# Smart_Lights_X4.net
KiCad netlist of a schematic drawn in EAGLE
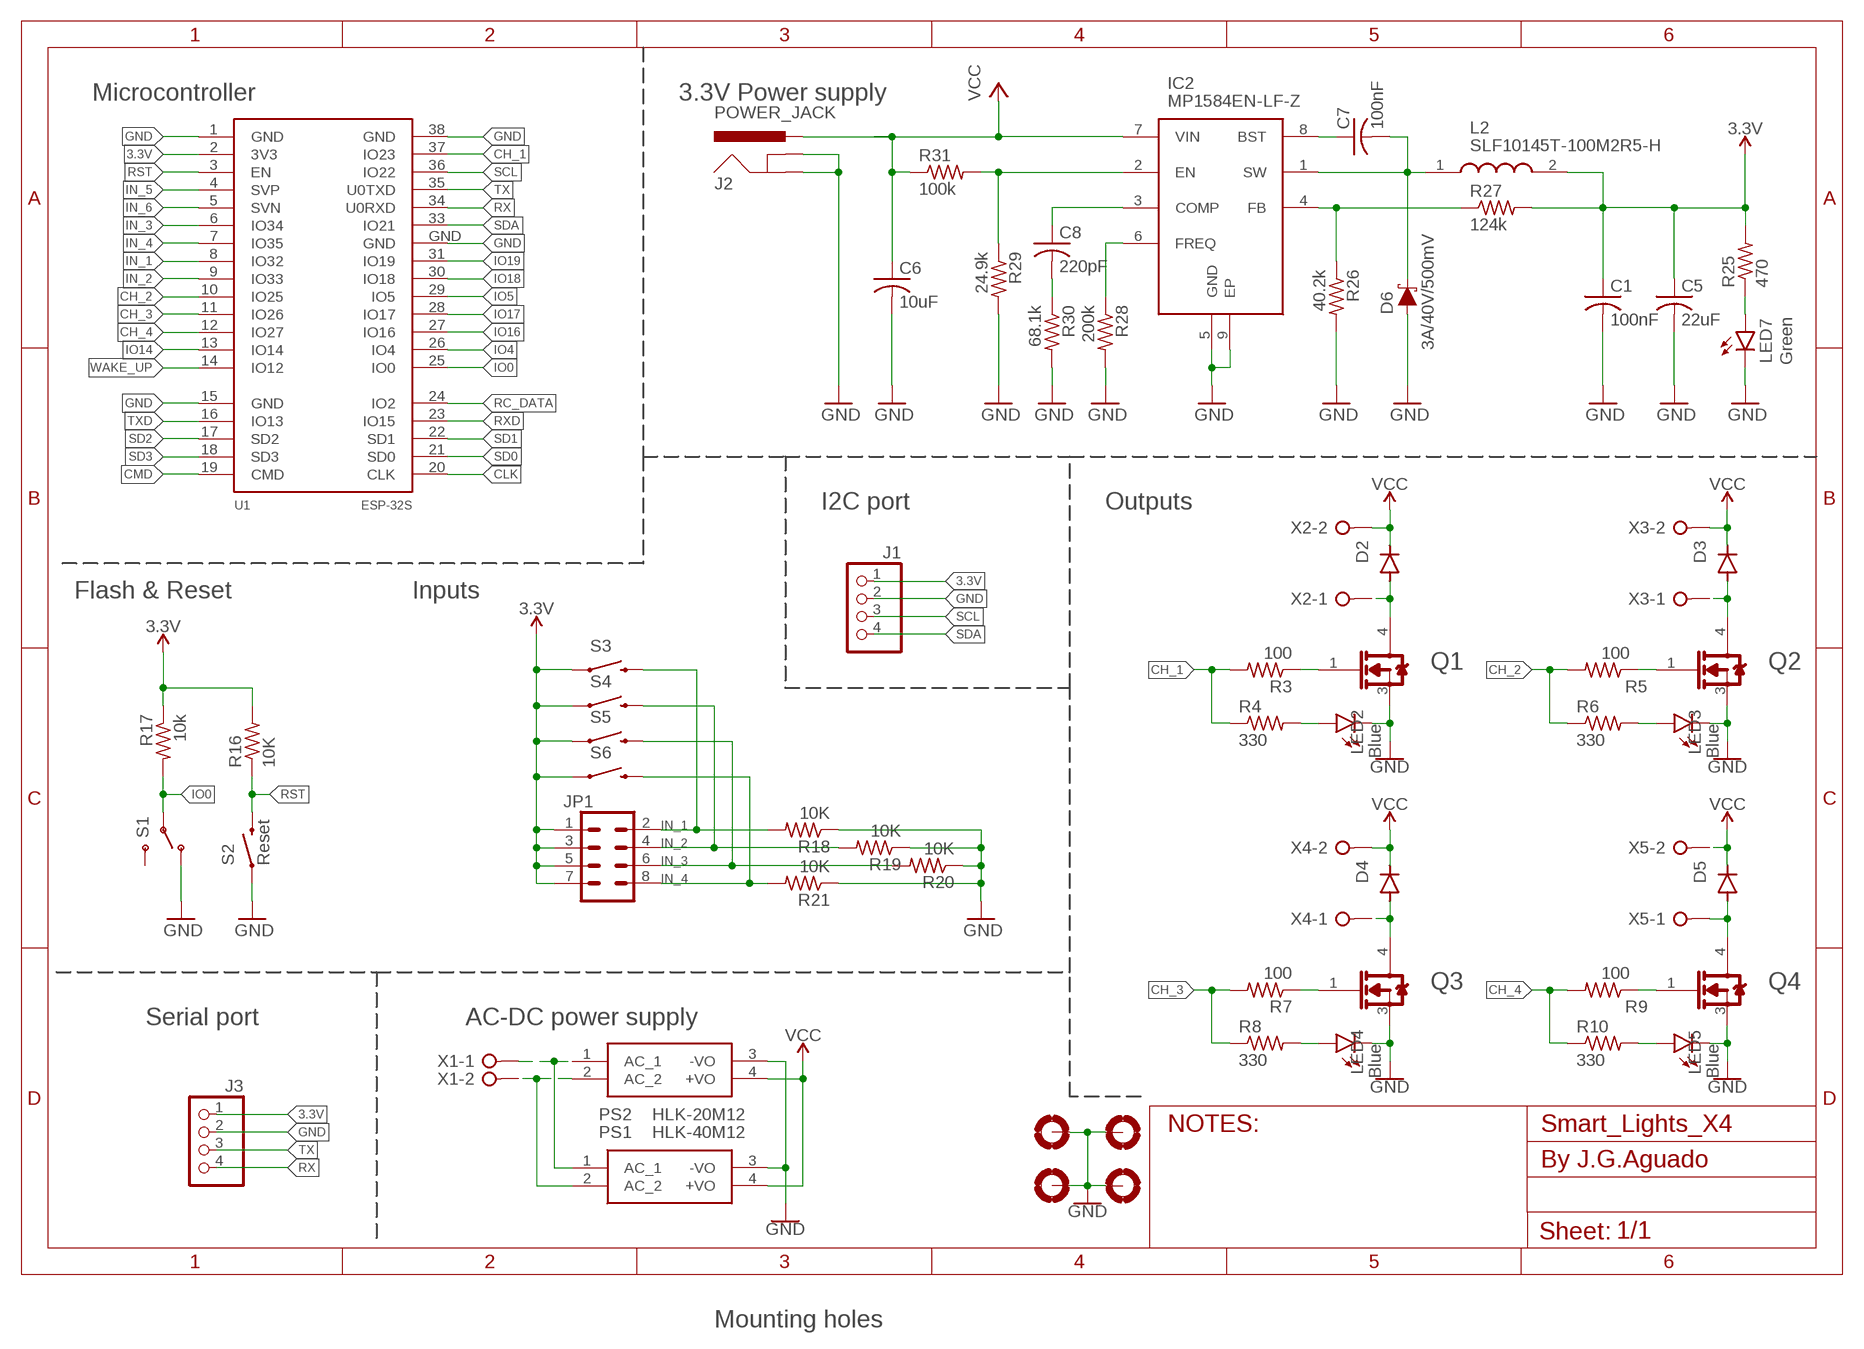
[diagram p0: schematic, sheet 1]

(export (version "E")
  (design (tool "Eeschema 10.0.6"))
  (components
    (comp (ref "C1")
      (value "100nF")
      (footprint "eagle-import:C0603")
      (libsource (lib "eagle-import") (part "C-USC0603"))
    )
    (comp (ref "C5")
      (value "22uF")
      (footprint "eagle-import:C0603")
      (libsource (lib "eagle-import") (part "C-USC0603"))
    )
    (comp (ref "C6")
      (value "10uF")
      (footprint "eagle-import:C0603")
      (libsource (lib "eagle-import") (part "C-USC0603"))
    )
    (comp (ref "C7")
      (value "100nF")
      (footprint "eagle-import:C0603")
      (libsource (lib "eagle-import") (part "C-USC0603"))
    )
    (comp (ref "C8")
      (value "220pF")
      (footprint "eagle-import:C0603")
      (libsource (lib "eagle-import") (part "C-USC0603"))
    )
    (comp (ref "D2")
      (value "DIODE-SOD123")
      (footprint "eagle-import:SOD123")
      (libsource (lib "eagle-import") (part "DIODE-SOD123"))
    )
    (comp (ref "D3")
      (value "DIODE-SOD123")
      (footprint "eagle-import:SOD123")
      (libsource (lib "eagle-import") (part "DIODE-SOD123"))
    )
    (comp (ref "D4")
      (value "DIODE-SOD123")
      (footprint "eagle-import:SOD123")
      (libsource (lib "eagle-import") (part "DIODE-SOD123"))
    )
    (comp (ref "D5")
      (value "DIODE-SOD123")
      (footprint "eagle-import:SOD123")
      (libsource (lib "eagle-import") (part "DIODE-SOD123"))
    )
    (comp (ref "D6")
      (value "3A/40V/500mV")
      (footprint "eagle-import:SMA-DIODE")
      (libsource (lib "eagle-import") (part "DIODE-SCHOTTKY-B340A"))
    )
    (comp (ref "FRAME1")
      (value "A4L-LOC")
      (footprint "eagle-import:92X87")
      (libsource (lib "eagle-import") (part "A4L-LOC"))
    )
    (comp (ref "IC2")
      (value "MP1584EN-LF-Z")
      (footprint "eagle-import:SOIC127P600X170-9N")
      (fields (field (name "MOUSER_PART_NUMBER") "946-MP1584ENLFZ"))
      (libsource (lib "eagle-import") (part "MP1584EN-LF-Z"))
    )
    (comp (ref "J1")
      (value "PINHD-1X4")
      (footprint "eagle-import:1X04")
      (libsource (lib "eagle-import") (part "PINHD-1X4"))
    )
    (comp (ref "J2")
      (value "POWER_JACK")
      (footprint "eagle-import:POWER_JACK_PTH")
      (libsource (lib "eagle-import") (part "POWER_JACK"))
    )
    (comp (ref "J3")
      (value "PINHD-1X4")
      (footprint "eagle-import:1X04")
      (libsource (lib "eagle-import") (part "PINHD-1X4"))
    )
    (comp (ref "JP1")
      (value "CONN_04X2")
      (footprint "eagle-import:2X4")
      (libsource (lib "eagle-import") (part "CONN_04X2"))
    )
    (comp (ref "L2")
      (value "SLF10145T-100M2R5-H")
      (footprint "eagle-import:SLF10145")
      (fields (field (name "MOUSER_PART_NUMBER") "810-SLF10145T100M2R5"))
      (libsource (lib "eagle-import") (part "SLF10145T-100M2R5-H"))
    )
    (comp (ref "LED2")
      (value "Blue")
      (footprint "eagle-import:SML0603")
      (libsource (lib "eagle-import") (part "LEDSML0603"))
    )
    (comp (ref "LED3")
      (value "Blue")
      (footprint "eagle-import:SML0603")
      (libsource (lib "eagle-import") (part "LEDSML0603"))
    )
    (comp (ref "LED4")
      (value "Blue")
      (footprint "eagle-import:SML0603")
      (libsource (lib "eagle-import") (part "LEDSML0603"))
    )
    (comp (ref "LED5")
      (value "Blue")
      (footprint "eagle-import:SML0603")
      (libsource (lib "eagle-import") (part "LEDSML0603"))
    )
    (comp (ref "LED7")
      (value "Green")
      (footprint "eagle-import:SML0603")
      (libsource (lib "eagle-import") (part "LEDSML0603"))
    )
    (comp (ref "PS1")
      (value "HLK-40M12")
      (footprint "eagle-import:HLK-40M12")
      (libsource (lib "eagle-import") (part "HLK-40M12"))
    )
    (comp (ref "PS2")
      (value "HLK-20M12")
      (footprint "eagle-import:HLK-20M12")
      (libsource (lib "eagle-import") (part "HLK-20M12"))
    )
    (comp (ref "Q1")
      (value "IRLR2905TRPBF")
      (footprint "eagle-import:INFINEON_TECHNOLOGIES_IRLR2905TRPBF_0")
      (fields
        (field (name "DIGIKEY_PART_NUMBER") "IRLR2905PBFCT-ND")
        (field (name "MF") "Infineon Technologies")
        (field (name "MOUSER_PART_NUMBER") "942-IRLR2905TRPBF")
      )
      (libsource (lib "eagle-import") (part "INFINEON_TECHNOLOGIES_IRLR2905TRPBFINFINEON_TECHNOLOGIES_IRLR2905TRPBF_0_0"))
    )
    (comp (ref "Q2")
      (value "IRLR2905TRPBF")
      (footprint "eagle-import:INFINEON_TECHNOLOGIES_IRLR2905TRPBF_0")
      (fields
        (field (name "DIGIKEY_PART_NUMBER") "IRLR2905PBFCT-ND")
        (field (name "MF") "Infineon Technologies")
        (field (name "MOUSER_PART_NUMBER") "942-IRLR2905TRPBF")
      )
      (libsource (lib "eagle-import") (part "INFINEON_TECHNOLOGIES_IRLR2905TRPBFINFINEON_TECHNOLOGIES_IRLR2905TRPBF_0_0"))
    )
    (comp (ref "Q3")
      (value "IRLR2905TRPBF")
      (footprint "eagle-import:INFINEON_TECHNOLOGIES_IRLR2905TRPBF_0")
      (fields
        (field (name "DIGIKEY_PART_NUMBER") "IRLR2905PBFCT-ND")
        (field (name "MF") "Infineon Technologies")
        (field (name "MOUSER_PART_NUMBER") "942-IRLR2905TRPBF")
      )
      (libsource (lib "eagle-import") (part "INFINEON_TECHNOLOGIES_IRLR2905TRPBFINFINEON_TECHNOLOGIES_IRLR2905TRPBF_0_0"))
    )
    (comp (ref "Q4")
      (value "IRLR2905TRPBF")
      (footprint "eagle-import:INFINEON_TECHNOLOGIES_IRLR2905TRPBF_0")
      (fields
        (field (name "DIGIKEY_PART_NUMBER") "IRLR2905PBFCT-ND")
        (field (name "MF") "Infineon Technologies")
        (field (name "MOUSER_PART_NUMBER") "942-IRLR2905TRPBF")
      )
      (libsource (lib "eagle-import") (part "INFINEON_TECHNOLOGIES_IRLR2905TRPBFINFINEON_TECHNOLOGIES_IRLR2905TRPBF_0_0"))
    )
    (comp (ref "R3")
      (value "100")
      (footprint "eagle-import:R0603")
      (libsource (lib "eagle-import") (part "R-US_R0603"))
    )
    (comp (ref "R4")
      (value "330")
      (footprint "eagle-import:R0603")
      (libsource (lib "eagle-import") (part "R-US_R0603"))
    )
    (comp (ref "R5")
      (value "100")
      (footprint "eagle-import:R0603")
      (libsource (lib "eagle-import") (part "R-US_R0603"))
    )
    (comp (ref "R6")
      (value "330")
      (footprint "eagle-import:R0603")
      (libsource (lib "eagle-import") (part "R-US_R0603"))
    )
    (comp (ref "R7")
      (value "100")
      (footprint "eagle-import:R0603")
      (libsource (lib "eagle-import") (part "R-US_R0603"))
    )
    (comp (ref "R8")
      (value "330")
      (footprint "eagle-import:R0603")
      (libsource (lib "eagle-import") (part "R-US_R0603"))
    )
    (comp (ref "R9")
      (value "100")
      (footprint "eagle-import:R0603")
      (libsource (lib "eagle-import") (part "R-US_R0603"))
    )
    (comp (ref "R10")
      (value "330")
      (footprint "eagle-import:R0603")
      (libsource (lib "eagle-import") (part "R-US_R0603"))
    )
    (comp (ref "R16")
      (value "10K")
      (footprint "eagle-import:R0603")
      (libsource (lib "eagle-import") (part "R-US_R0603"))
    )
    (comp (ref "R17")
      (value "10k")
      (footprint "eagle-import:R0603")
      (libsource (lib "eagle-import") (part "R-US_R0603"))
    )
    (comp (ref "R18")
      (value "10K")
      (footprint "eagle-import:R0603")
      (libsource (lib "eagle-import") (part "R-US_R0603"))
    )
    (comp (ref "R19")
      (value "10K")
      (footprint "eagle-import:R0603")
      (libsource (lib "eagle-import") (part "R-US_R0603"))
    )
    (comp (ref "R20")
      (value "10K")
      (footprint "eagle-import:R0603")
      (libsource (lib "eagle-import") (part "R-US_R0603"))
    )
    (comp (ref "R21")
      (value "10K")
      (footprint "eagle-import:R0603")
      (libsource (lib "eagle-import") (part "R-US_R0603"))
    )
    (comp (ref "R25")
      (value "470")
      (footprint "eagle-import:R0603")
      (libsource (lib "eagle-import") (part "R-US_R0603"))
    )
    (comp (ref "R26")
      (value "40.2k")
      (footprint "eagle-import:R0603")
      (libsource (lib "eagle-import") (part "R-US_R0603"))
    )
    (comp (ref "R27")
      (value "124k")
      (footprint "eagle-import:R0603")
      (libsource (lib "eagle-import") (part "R-US_R0603"))
    )
    (comp (ref "R28")
      (value "200k")
      (footprint "eagle-import:R0603")
      (libsource (lib "eagle-import") (part "R-US_R0603"))
    )
    (comp (ref "R29")
      (value "24.9k")
      (footprint "eagle-import:R0603")
      (libsource (lib "eagle-import") (part "R-US_R0603"))
    )
    (comp (ref "R30")
      (value "68.1k")
      (footprint "eagle-import:R0603")
      (libsource (lib "eagle-import") (part "R-US_R0603"))
    )
    (comp (ref "R31")
      (value "100k")
      (footprint "eagle-import:R0603")
      (libsource (lib "eagle-import") (part "R-US_R0603"))
    )
    (comp (ref "S1")
      (value "SWITCH_SPDT")
      (footprint "eagle-import:KPS-1290")
      (libsource (lib "eagle-import") (part "SWITCH_SPDT"))
    )
    (comp (ref "S2")
      (value "Reset")
      (footprint "eagle-import:TACTILE_SWITCH_TALL")
      (libsource (lib "eagle-import") (part "SWITCH-MOMENTARY-2SMD-4"))
    )
    (comp (ref "S3")
      (value "Reset")
      (footprint "eagle-import:TACTILE_SWITCH_TALL")
      (libsource (lib "eagle-import") (part "SWITCH-MOMENTARY-2SMD-4"))
    )
    (comp (ref "S4")
      (value "Reset")
      (footprint "eagle-import:TACTILE_SWITCH_TALL")
      (libsource (lib "eagle-import") (part "SWITCH-MOMENTARY-2SMD-4"))
    )
    (comp (ref "S5")
      (value "Reset")
      (footprint "eagle-import:TACTILE_SWITCH_TALL")
      (libsource (lib "eagle-import") (part "SWITCH-MOMENTARY-2SMD-4"))
    )
    (comp (ref "S6")
      (value "Reset")
      (footprint "eagle-import:TACTILE_SWITCH_TALL")
      (libsource (lib "eagle-import") (part "SWITCH-MOMENTARY-2SMD-4"))
    )
    (comp (ref "U1")
      (value "ESP-32S")
      (footprint "eagle-import:ESP-32S")
      (libsource (lib "eagle-import") (part "ESP-32S"))
    )
    (comp (ref "X1")
      (value "W237-02P")
      (footprint "eagle-import:W237-132")
      (libsource (lib "eagle-import") (part "W237-02P"))
    )
    (comp (ref "X2")
      (value "W237-02P")
      (footprint "eagle-import:W237-132")
      (libsource (lib "eagle-import") (part "W237-02P"))
    )
    (comp (ref "X3")
      (value "W237-02P")
      (footprint "eagle-import:W237-132")
      (libsource (lib "eagle-import") (part "W237-02P"))
    )
    (comp (ref "X4")
      (value "W237-02P")
      (footprint "eagle-import:W237-132")
      (libsource (lib "eagle-import") (part "W237-02P"))
    )
    (comp (ref "X5")
      (value "W237-02P")
      (footprint "eagle-import:W237-132")
      (libsource (lib "eagle-import") (part "W237-02P"))
    )
  )
  (nets
    (net (code "1") (name "3.3V") (class "Default")
      (node (ref "C1") (pin "1") (pinfunction "1_1") (pintype "passive"))
      (node (ref "C5") (pin "1") (pinfunction "1_1") (pintype "passive"))
      (node (ref "J1") (pin "1") (pinfunction "1_1") (pintype "passive"))
      (node (ref "J3") (pin "1") (pinfunction "1_1") (pintype "passive"))
      (node (ref "JP1") (pin "1") (pinfunction "1_1") (pintype "passive"))
      (node (ref "JP1") (pin "3") (pinfunction "3_3") (pintype "passive"))
      (node (ref "JP1") (pin "5") (pinfunction "5_5") (pintype "passive"))
      (node (ref "JP1") (pin "7") (pinfunction "7_7") (pintype "passive"))
      (node (ref "L2") (pin "2") (pinfunction "2_2") (pintype "bidirectional"))
      (node (ref "R16") (pin "2") (pinfunction "2_2") (pintype "passive"))
      (node (ref "R17") (pin "1") (pinfunction "1_1") (pintype "passive"))
      (node (ref "R25") (pin "2") (pinfunction "2_2") (pintype "passive"))
      (node (ref "R27") (pin "2") (pinfunction "2_2") (pintype "passive"))
      (node (ref "S3") (pin "A2") (pinfunction "1_A2") (pintype "passive"))
      (node (ref "S4") (pin "A2") (pinfunction "1_A2") (pintype "passive"))
      (node (ref "S5") (pin "A2") (pinfunction "1_A2") (pintype "passive"))
      (node (ref "S6") (pin "A2") (pinfunction "1_A2") (pintype "passive"))
      (node (ref "U1") (pin "2") (pinfunction "3V3_2") (pintype "power_in"))
    )
    (net (code "2") (name "CH_1") (class "Default")
      (node (ref "R3") (pin "2") (pinfunction "2_2") (pintype "passive"))
      (node (ref "R4") (pin "1") (pinfunction "1_1") (pintype "passive"))
      (node (ref "U1") (pin "37") (pinfunction "IO23_37") (pintype "bidirectional"))
    )
    (net (code "3") (name "CH_2") (class "Default")
      (node (ref "R5") (pin "2") (pinfunction "2_2") (pintype "passive"))
      (node (ref "R6") (pin "1") (pinfunction "1_1") (pintype "passive"))
      (node (ref "U1") (pin "10") (pinfunction "IO25_10") (pintype "bidirectional"))
    )
    (net (code "4") (name "CH_3") (class "Default")
      (node (ref "R7") (pin "2") (pinfunction "2_2") (pintype "passive"))
      (node (ref "R8") (pin "1") (pinfunction "1_1") (pintype "passive"))
      (node (ref "U1") (pin "11") (pinfunction "IO26_11") (pintype "bidirectional"))
    )
    (net (code "5") (name "CH_4") (class "Default")
      (node (ref "R10") (pin "1") (pinfunction "1_1") (pintype "passive"))
      (node (ref "R9") (pin "2") (pinfunction "2_2") (pintype "passive"))
      (node (ref "U1") (pin "12") (pinfunction "IO27_12") (pintype "bidirectional"))
    )
    (net (code "6") (name "CLK") (class "Default")
      (node (ref "U1") (pin "20") (pinfunction "CLK_20") (pintype "bidirectional"))
    )
    (net (code "7") (name "CMD") (class "Default")
      (node (ref "U1") (pin "19") (pinfunction "CMD_19") (pintype "bidirectional"))
    )
    (net (code "8") (name "GND") (class "Default")
      (node (ref "C1") (pin "2") (pinfunction "2_2") (pintype "passive"))
      (node (ref "C5") (pin "2") (pinfunction "2_2") (pintype "passive"))
      (node (ref "C6") (pin "2") (pinfunction "2_2") (pintype "passive"))
      (node (ref "D6") (pin "A") (pinfunction "A_A") (pintype "passive"))
      (node (ref "FRAME1") (pin "B3,1") (pinfunction "MOUNT_B3,1") (pintype "passive"))
      (node (ref "FRAME1") (pin "B3,2") (pinfunction "MOUNT1_B3,2") (pintype "passive"))
      (node (ref "FRAME1") (pin "B3,3") (pinfunction "MOUNT2_B3,3") (pintype "passive"))
      (node (ref "FRAME1") (pin "B3,6") (pinfunction "MOUNT3_B3,6") (pintype "passive"))
      (node (ref "IC2") (pin "5") (pinfunction "GND_5") (pintype "power_in"))
      (node (ref "IC2") (pin "9") (pinfunction "EP_9") (pintype "bidirectional"))
      (node (ref "J1") (pin "2") (pinfunction "2_2") (pintype "passive"))
      (node (ref "J2") (pin "GND") (pinfunction "GND_GND") (pintype "bidirectional"))
      (node (ref "J2") (pin "GNDBREAK") (pinfunction "GNDBREAK_GNDBREAK") (pintype "bidirectional"))
      (node (ref "J3") (pin "2") (pinfunction "2_2") (pintype "passive"))
      (node (ref "LED2") (pin "C") (pinfunction "C_C") (pintype "passive"))
      (node (ref "LED3") (pin "C") (pinfunction "C_C") (pintype "passive"))
      (node (ref "LED4") (pin "C") (pinfunction "C_C") (pintype "passive"))
      (node (ref "LED5") (pin "C") (pinfunction "C_C") (pintype "passive"))
      (node (ref "LED7") (pin "C") (pinfunction "C_C") (pintype "passive"))
      (node (ref "PS1") (pin "3") (pinfunction "-VO_3") (pintype "bidirectional"))
      (node (ref "PS2") (pin "3") (pinfunction "-VO_3") (pintype "bidirectional"))
      (node (ref "Q1") (pin "3") (pinfunction "SOURCE_3") (pintype "passive"))
      (node (ref "Q2") (pin "3") (pinfunction "SOURCE_3") (pintype "passive"))
      (node (ref "Q3") (pin "3") (pinfunction "SOURCE_3") (pintype "passive"))
      (node (ref "Q4") (pin "3") (pinfunction "SOURCE_3") (pintype "passive"))
      (node (ref "R18") (pin "1") (pinfunction "1_1") (pintype "passive"))
      (node (ref "R19") (pin "1") (pinfunction "1_1") (pintype "passive"))
      (node (ref "R20") (pin "1") (pinfunction "1_1") (pintype "passive"))
      (node (ref "R21") (pin "1") (pinfunction "1_1") (pintype "passive"))
      (node (ref "R26") (pin "2") (pinfunction "2_2") (pintype "passive"))
      (node (ref "R28") (pin "2") (pinfunction "2_2") (pintype "passive"))
      (node (ref "R29") (pin "2") (pinfunction "2_2") (pintype "passive"))
      (node (ref "R30") (pin "2") (pinfunction "2_2") (pintype "passive"))
      (node (ref "S1") (pin "O") (pinfunction "O_O") (pintype "passive"))
      (node (ref "S2") (pin "A2") (pinfunction "1_A2") (pintype "passive"))
      (node (ref "U1") (pin "1") (pinfunction "GND_1") (pintype "power_in"))
      (node (ref "U1") (pin "15") (pinfunction "GND_15") (pintype "power_in"))
      (node (ref "U1") (pin "38") (pinfunction "GND_38") (pintype "power_in"))
      (node (ref "U1") (pin "GND") (pinfunction "GND_GND") (pintype "power_in"))
    )
    (net (code "9") (name "IN_1") (class "Default")
      (node (ref "JP1") (pin "2") (pinfunction "2_2") (pintype "passive"))
      (node (ref "R18") (pin "2") (pinfunction "2_2") (pintype "passive"))
      (node (ref "S3") (pin "B2") (pinfunction "2_B2") (pintype "passive"))
      (node (ref "U1") (pin "8") (pinfunction "IO32_8") (pintype "bidirectional"))
    )
    (net (code "10") (name "IN_2") (class "Default")
      (node (ref "JP1") (pin "4") (pinfunction "4_4") (pintype "passive"))
      (node (ref "R19") (pin "2") (pinfunction "2_2") (pintype "passive"))
      (node (ref "S4") (pin "B2") (pinfunction "2_B2") (pintype "passive"))
      (node (ref "U1") (pin "9") (pinfunction "IO33_9") (pintype "bidirectional"))
    )
    (net (code "11") (name "IN_3") (class "Default")
      (node (ref "JP1") (pin "6") (pinfunction "6_6") (pintype "passive"))
      (node (ref "R20") (pin "2") (pinfunction "2_2") (pintype "passive"))
      (node (ref "S5") (pin "B2") (pinfunction "2_B2") (pintype "passive"))
      (node (ref "U1") (pin "6") (pinfunction "IO34_6") (pintype "bidirectional"))
    )
    (net (code "12") (name "IN_4") (class "Default")
      (node (ref "JP1") (pin "8") (pinfunction "8_8") (pintype "passive"))
      (node (ref "R21") (pin "2") (pinfunction "2_2") (pintype "passive"))
      (node (ref "S6") (pin "B2") (pinfunction "2_B2") (pintype "passive"))
      (node (ref "U1") (pin "7") (pinfunction "IO35_7") (pintype "bidirectional"))
    )
    (net (code "13") (name "IN_5") (class "Default")
      (node (ref "U1") (pin "4") (pinfunction "SVP_4") (pintype "bidirectional"))
    )
    (net (code "14") (name "IN_6") (class "Default")
      (node (ref "U1") (pin "5") (pinfunction "SVN_5") (pintype "bidirectional"))
    )
    (net (code "15") (name "IO0") (class "Default")
      (node (ref "R17") (pin "2") (pinfunction "2_2") (pintype "passive"))
      (node (ref "S1") (pin "P") (pinfunction "P_P") (pintype "passive"))
      (node (ref "U1") (pin "25") (pinfunction "IO0_25") (pintype "bidirectional"))
    )
    (net (code "16") (name "IO4") (class "Default")
      (node (ref "U1") (pin "26") (pinfunction "IO4_26") (pintype "bidirectional"))
    )
    (net (code "17") (name "IO5") (class "Default")
      (node (ref "U1") (pin "29") (pinfunction "IO5_29") (pintype "bidirectional"))
    )
    (net (code "18") (name "IO14") (class "Default")
      (node (ref "U1") (pin "13") (pinfunction "IO14_13") (pintype "bidirectional"))
    )
    (net (code "19") (name "IO16") (class "Default")
      (node (ref "U1") (pin "27") (pinfunction "IO16_27") (pintype "bidirectional"))
    )
    (net (code "20") (name "IO17") (class "Default")
      (node (ref "U1") (pin "28") (pinfunction "IO17_28") (pintype "bidirectional"))
    )
    (net (code "21") (name "IO18") (class "Default")
      (node (ref "U1") (pin "30") (pinfunction "IO18_30") (pintype "bidirectional"))
    )
    (net (code "22") (name "IO19") (class "Default")
      (node (ref "U1") (pin "31") (pinfunction "IO19_31") (pintype "bidirectional"))
    )
    (net (code "23") (name "Net-(C8-Pad2)") (class "Default")
      (node (ref "C8") (pin "2") (pinfunction "2_2") (pintype "passive"))
      (node (ref "R30") (pin "1") (pinfunction "1_1") (pintype "passive"))
    )
    (net (code "24") (name "Net-(IC2-BST)") (class "Default")
      (node (ref "C7") (pin "1") (pinfunction "1_1") (pintype "passive"))
      (node (ref "IC2") (pin "8") (pinfunction "BST_8") (pintype "input"))
    )
    (net (code "25") (name "Net-(IC2-COMP)") (class "Default")
      (node (ref "C8") (pin "1") (pinfunction "1_1") (pintype "passive"))
      (node (ref "IC2") (pin "3") (pinfunction "COMP_3") (pintype "bidirectional"))
    )
    (net (code "26") (name "Net-(IC2-EN)") (class "Default")
      (node (ref "IC2") (pin "2") (pinfunction "EN_2") (pintype "input"))
      (node (ref "R29") (pin "1") (pinfunction "1_1") (pintype "passive"))
      (node (ref "R31") (pin "2") (pinfunction "2_2") (pintype "passive"))
    )
    (net (code "27") (name "Net-(IC2-FB)") (class "Default")
      (node (ref "IC2") (pin "4") (pinfunction "FB_4") (pintype "input"))
      (node (ref "R26") (pin "1") (pinfunction "1_1") (pintype "passive"))
      (node (ref "R27") (pin "1") (pinfunction "1_1") (pintype "passive"))
    )
    (net (code "28") (name "Net-(IC2-FREQ)") (class "Default")
      (node (ref "IC2") (pin "6") (pinfunction "FREQ_6") (pintype "input"))
      (node (ref "R28") (pin "1") (pinfunction "1_1") (pintype "passive"))
    )
    (net (code "29") (name "Net-(IC2-SW)") (class "Default")
      (node (ref "C7") (pin "2") (pinfunction "2_2") (pintype "passive"))
      (node (ref "D6") (pin "C") (pinfunction "C_C") (pintype "passive"))
      (node (ref "IC2") (pin "1") (pinfunction "SW_1") (pintype "output"))
      (node (ref "L2") (pin "1") (pinfunction "1_1") (pintype "bidirectional"))
    )
    (net (code "30") (name "Net-(LED2-PadA)") (class "Default")
      (node (ref "LED2") (pin "A") (pinfunction "A_A") (pintype "passive"))
      (node (ref "R4") (pin "2") (pinfunction "2_2") (pintype "passive"))
    )
    (net (code "31") (name "Net-(LED3-PadA)") (class "Default")
      (node (ref "LED3") (pin "A") (pinfunction "A_A") (pintype "passive"))
      (node (ref "R6") (pin "2") (pinfunction "2_2") (pintype "passive"))
    )
    (net (code "32") (name "Net-(LED4-PadA)") (class "Default")
      (node (ref "LED4") (pin "A") (pinfunction "A_A") (pintype "passive"))
      (node (ref "R8") (pin "2") (pinfunction "2_2") (pintype "passive"))
    )
    (net (code "33") (name "Net-(LED5-PadA)") (class "Default")
      (node (ref "LED5") (pin "A") (pinfunction "A_A") (pintype "passive"))
      (node (ref "R10") (pin "2") (pinfunction "2_2") (pintype "passive"))
    )
    (net (code "34") (name "Net-(LED7-PadA)") (class "Default")
      (node (ref "LED7") (pin "A") (pinfunction "A_A") (pintype "passive"))
      (node (ref "R25") (pin "1") (pinfunction "1_1") (pintype "passive"))
    )
    (net (code "35") (name "Net-(PS1-AC_1)") (class "Default")
      (node (ref "PS1") (pin "1") (pinfunction "AC_1_1") (pintype "bidirectional"))
      (node (ref "PS2") (pin "1") (pinfunction "AC_1_1") (pintype "bidirectional"))
      (node (ref "X1") (pin "1") (pinfunction "KL_1") (pintype "passive"))
    )
    (net (code "36") (name "Net-(PS1-AC_2)") (class "Default")
      (node (ref "PS1") (pin "2") (pinfunction "AC_2_2") (pintype "bidirectional"))
      (node (ref "PS2") (pin "2") (pinfunction "AC_2_2") (pintype "bidirectional"))
      (node (ref "X1") (pin "2") (pinfunction "KL_2") (pintype "passive"))
    )
    (net (code "37") (name "Net-(Q1-DRAIN)") (class "Default")
      (node (ref "D2") (pin "A") (pinfunction "A_A") (pintype "passive"))
      (node (ref "Q1") (pin "4") (pinfunction "DRAIN_4") (pintype "passive"))
      (node (ref "X2") (pin "1") (pinfunction "KL_1") (pintype "passive"))
    )
    (net (code "38") (name "Net-(Q1-GATE)") (class "Default")
      (node (ref "Q1") (pin "1") (pinfunction "GATE_1") (pintype "passive"))
      (node (ref "R3") (pin "1") (pinfunction "1_1") (pintype "passive"))
    )
    (net (code "39") (name "Net-(Q2-DRAIN)") (class "Default")
      (node (ref "D3") (pin "A") (pinfunction "A_A") (pintype "passive"))
      (node (ref "Q2") (pin "4") (pinfunction "DRAIN_4") (pintype "passive"))
      (node (ref "X3") (pin "1") (pinfunction "KL_1") (pintype "passive"))
    )
    (net (code "40") (name "Net-(Q2-GATE)") (class "Default")
      (node (ref "Q2") (pin "1") (pinfunction "GATE_1") (pintype "passive"))
      (node (ref "R5") (pin "1") (pinfunction "1_1") (pintype "passive"))
    )
    (net (code "41") (name "Net-(Q3-DRAIN)") (class "Default")
      (node (ref "D4") (pin "A") (pinfunction "A_A") (pintype "passive"))
      (node (ref "Q3") (pin "4") (pinfunction "DRAIN_4") (pintype "passive"))
      (node (ref "X4") (pin "1") (pinfunction "KL_1") (pintype "passive"))
    )
    (net (code "42") (name "Net-(Q3-GATE)") (class "Default")
      (node (ref "Q3") (pin "1") (pinfunction "GATE_1") (pintype "passive"))
      (node (ref "R7") (pin "1") (pinfunction "1_1") (pintype "passive"))
    )
    (net (code "43") (name "Net-(Q4-DRAIN)") (class "Default")
      (node (ref "D5") (pin "A") (pinfunction "A_A") (pintype "passive"))
      (node (ref "Q4") (pin "4") (pinfunction "DRAIN_4") (pintype "passive"))
      (node (ref "X5") (pin "1") (pinfunction "KL_1") (pintype "passive"))
    )
    (net (code "44") (name "Net-(Q4-GATE)") (class "Default")
      (node (ref "Q4") (pin "1") (pinfunction "GATE_1") (pintype "passive"))
      (node (ref "R9") (pin "1") (pinfunction "1_1") (pintype "passive"))
    )
    (net (code "45") (name "RC_DATA") (class "Default")
      (node (ref "U1") (pin "24") (pinfunction "IO2_24") (pintype "bidirectional"))
    )
    (net (code "46") (name "RST") (class "Default")
      (node (ref "R16") (pin "1") (pinfunction "1_1") (pintype "passive"))
      (node (ref "S2") (pin "B2") (pinfunction "2_B2") (pintype "passive"))
      (node (ref "U1") (pin "3") (pinfunction "EN_3") (pintype "input"))
    )
    (net (code "47") (name "RX") (class "Default")
      (node (ref "J3") (pin "4") (pinfunction "4_4") (pintype "passive"))
      (node (ref "U1") (pin "34") (pinfunction "U0RXD_34") (pintype "bidirectional"))
    )
    (net (code "48") (name "RXD") (class "Default")
      (node (ref "U1") (pin "23") (pinfunction "IO15_23") (pintype "bidirectional"))
    )
    (net (code "49") (name "SCL") (class "Default")
      (node (ref "J1") (pin "3") (pinfunction "3_3") (pintype "passive"))
      (node (ref "U1") (pin "36") (pinfunction "IO22_36") (pintype "bidirectional"))
    )
    (net (code "50") (name "SD0") (class "Default")
      (node (ref "U1") (pin "21") (pinfunction "SD0_21") (pintype "bidirectional"))
    )
    (net (code "51") (name "SD1") (class "Default")
      (node (ref "U1") (pin "22") (pinfunction "SD1_22") (pintype "bidirectional"))
    )
    (net (code "52") (name "SD2") (class "Default")
      (node (ref "U1") (pin "17") (pinfunction "SD2_17") (pintype "bidirectional"))
    )
    (net (code "53") (name "SD3") (class "Default")
      (node (ref "U1") (pin "18") (pinfunction "SD3_18") (pintype "bidirectional"))
    )
    (net (code "54") (name "SDA") (class "Default")
      (node (ref "J1") (pin "4") (pinfunction "4_4") (pintype "passive"))
      (node (ref "U1") (pin "33") (pinfunction "IO21_33") (pintype "bidirectional"))
    )
    (net (code "55") (name "TX") (class "Default")
      (node (ref "J3") (pin "3") (pinfunction "3_3") (pintype "passive"))
      (node (ref "U1") (pin "35") (pinfunction "U0TXD_35") (pintype "bidirectional"))
    )
    (net (code "56") (name "TXD") (class "Default")
      (node (ref "U1") (pin "16") (pinfunction "IO13_16") (pintype "bidirectional"))
    )
    (net (code "57") (name "VCC") (class "Default")
      (node (ref "C6") (pin "1") (pinfunction "1_1") (pintype "passive"))
      (node (ref "D2") (pin "C") (pinfunction "C_C") (pintype "passive"))
      (node (ref "D3") (pin "C") (pinfunction "C_C") (pintype "passive"))
      (node (ref "D4") (pin "C") (pinfunction "C_C") (pintype "passive"))
      (node (ref "D5") (pin "C") (pinfunction "C_C") (pintype "passive"))
      (node (ref "IC2") (pin "7") (pinfunction "VIN_7") (pintype "power_in"))
      (node (ref "J2") (pin "PWR") (pinfunction "PWR_PWR") (pintype "bidirectional"))
      (node (ref "PS1") (pin "4") (pinfunction "+VO_4") (pintype "bidirectional"))
      (node (ref "PS2") (pin "4") (pinfunction "+VO_4") (pintype "bidirectional"))
      (node (ref "R31") (pin "1") (pinfunction "1_1") (pintype "passive"))
      (node (ref "X2") (pin "2") (pinfunction "KL_2") (pintype "passive"))
      (node (ref "X3") (pin "2") (pinfunction "KL_2") (pintype "passive"))
      (node (ref "X4") (pin "2") (pinfunction "KL_2") (pintype "passive"))
      (node (ref "X5") (pin "2") (pinfunction "KL_2") (pintype "passive"))
    )
    (net (code "58") (name "WAKE_UP") (class "Default")
      (node (ref "U1") (pin "14") (pinfunction "IO12_14") (pintype "bidirectional"))
    )
    (net (code "59") (name "unconnected-(S1-PadS)") (class "Default")
      (node (ref "S1") (pin "S") (pinfunction "S_S") (pintype "passive"))
    )
  )
)
